# discretefpga.net
KiCad netlist of a schematic drawn in EAGLE
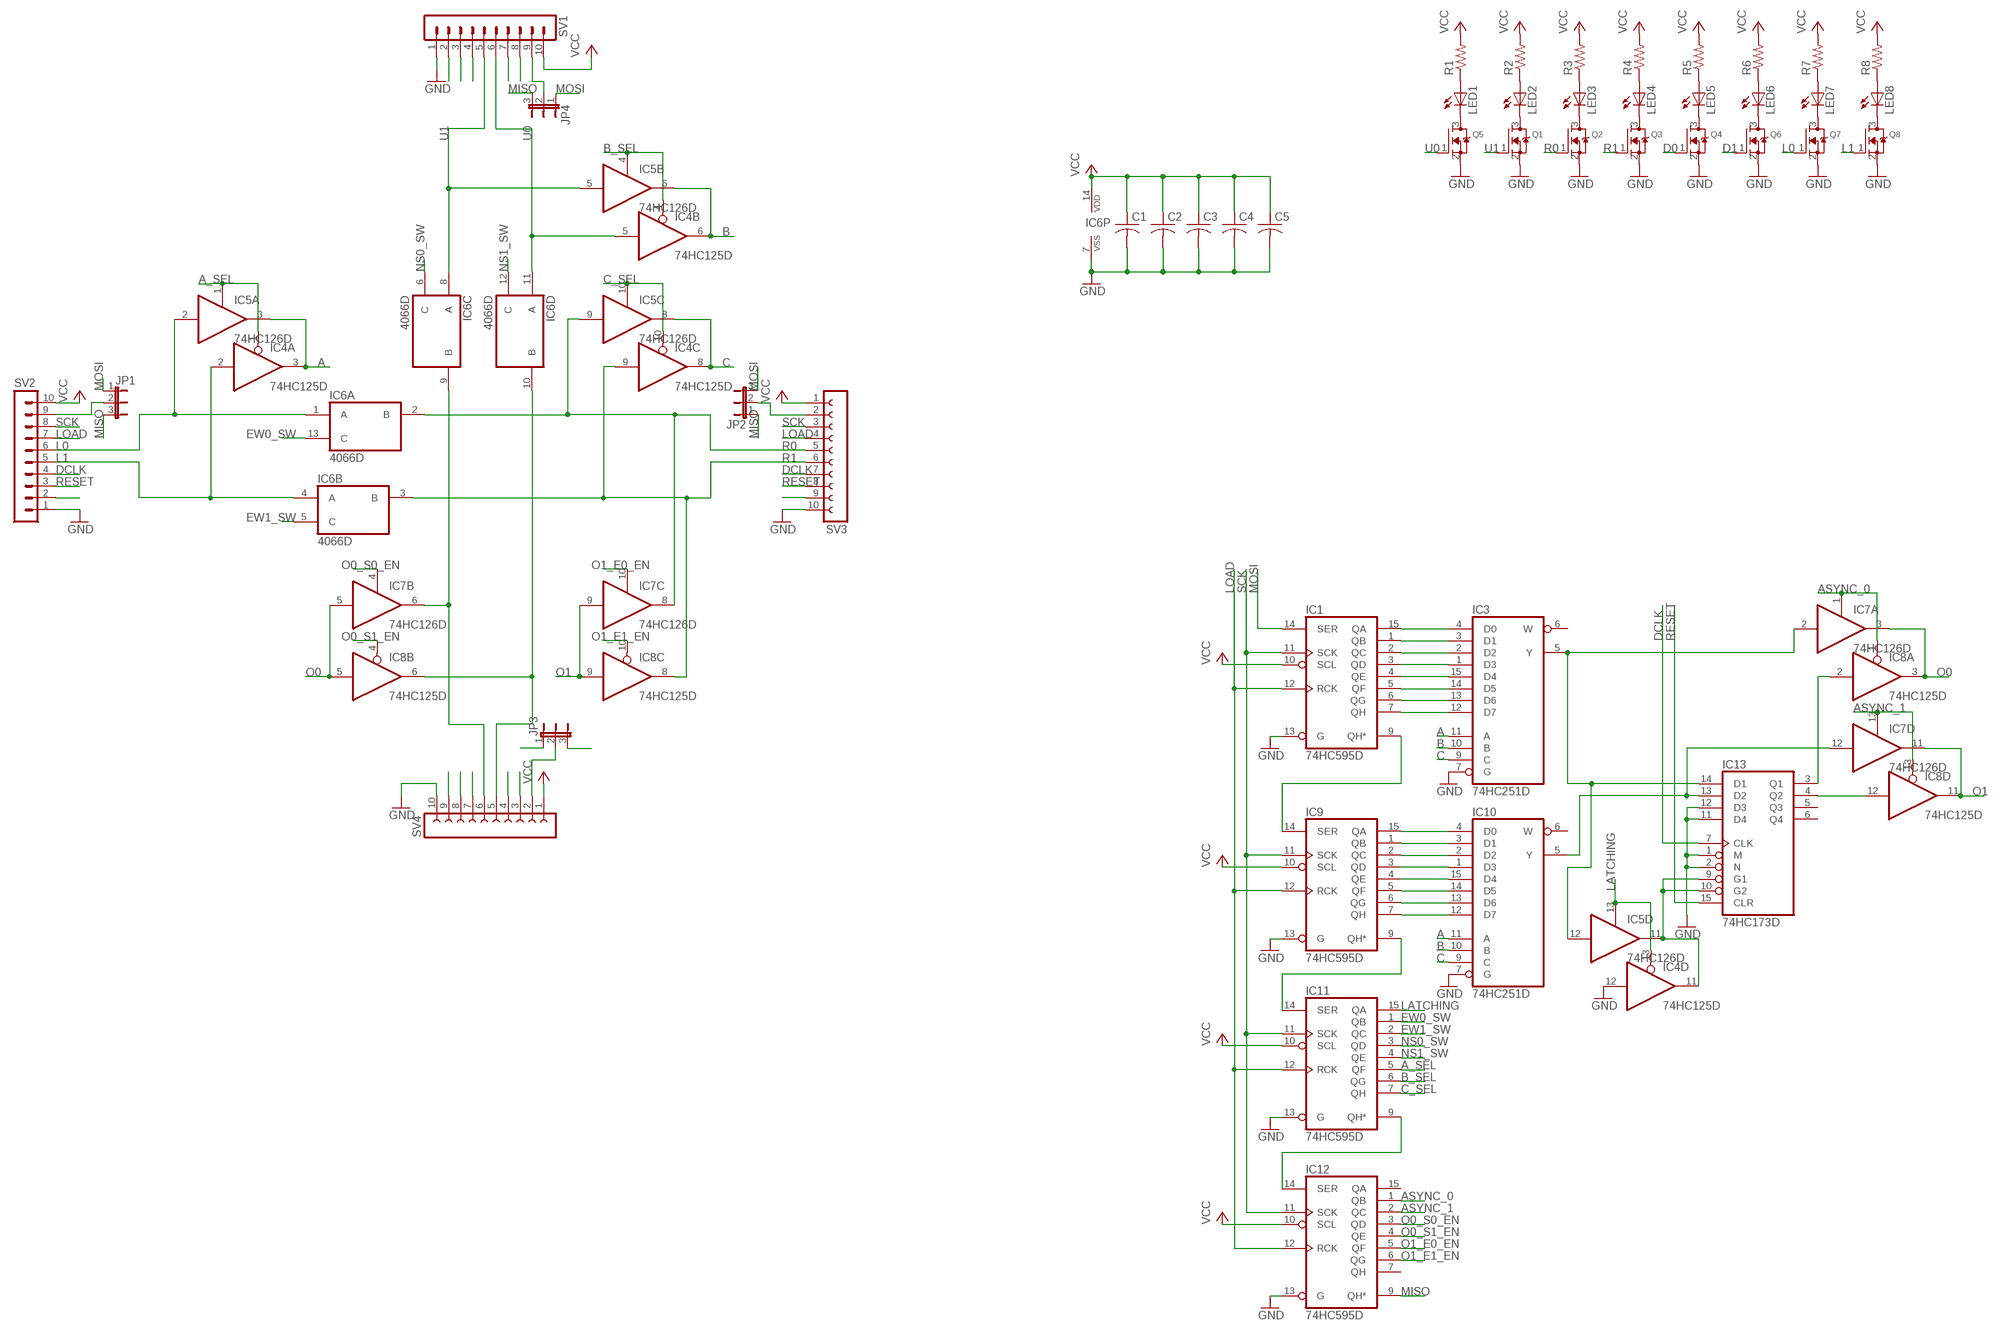
[diagram p0: schematic, sheet 1]

(export (version "E")
  (design (tool "Eeschema 10.0.6"))
  (components
    (comp (ref "C1")
      (value "C-USC0805")
      (footprint "eagle-import:C0805")
      (libsource (lib "eagle-import") (part "C-USC0805"))
    )
    (comp (ref "C2")
      (value "C-USC0805")
      (footprint "eagle-import:C0805")
      (libsource (lib "eagle-import") (part "C-USC0805"))
    )
    (comp (ref "C3")
      (value "C-USC0805")
      (footprint "eagle-import:C0805")
      (libsource (lib "eagle-import") (part "C-USC0805"))
    )
    (comp (ref "C4")
      (value "C-USC0805")
      (footprint "eagle-import:C0805")
      (libsource (lib "eagle-import") (part "C-USC0805"))
    )
    (comp (ref "C5")
      (value "C-USC0805")
      (footprint "eagle-import:C0805")
      (libsource (lib "eagle-import") (part "C-USC0805"))
    )
    (comp (ref "IC1")
      (value "74HC595D")
      (footprint "eagle-import:SO16")
      (libsource (lib "eagle-import") (part "74595DHC"))
    )
    (comp (ref "IC3")
      (value "74HC251D")
      (footprint "eagle-import:SO16")
      (libsource (lib "eagle-import") (part "74251DHC"))
    )
    (comp (ref "IC4")
      (value "74HC125D")
      (footprint "eagle-import:SO14")
      (libsource (lib "eagle-import") (part "74125DHC"))
    )
    (comp (ref "IC5")
      (value "74HC126D")
      (footprint "eagle-import:SO14")
      (libsource (lib "eagle-import") (part "74126DHC"))
    )
    (comp (ref "IC6")
      (value "4066D")
      (footprint "eagle-import:SO14")
      (libsource (lib "eagle-import") (part "4066D"))
    )
    (comp (ref "IC7")
      (value "74HC126D")
      (footprint "eagle-import:SO14")
      (libsource (lib "eagle-import") (part "74126DHC"))
    )
    (comp (ref "IC8")
      (value "74HC125D")
      (footprint "eagle-import:SO14")
      (libsource (lib "eagle-import") (part "74125DHC"))
    )
    (comp (ref "IC9")
      (value "74HC595D")
      (footprint "eagle-import:SO16")
      (libsource (lib "eagle-import") (part "74595DHC"))
    )
    (comp (ref "IC10")
      (value "74HC251D")
      (footprint "eagle-import:SO16")
      (libsource (lib "eagle-import") (part "74251DHC"))
    )
    (comp (ref "IC11")
      (value "74HC595D")
      (footprint "eagle-import:SO16")
      (libsource (lib "eagle-import") (part "74595DHC"))
    )
    (comp (ref "IC12")
      (value "74HC595D")
      (footprint "eagle-import:SO16")
      (libsource (lib "eagle-import") (part "74595DHC"))
    )
    (comp (ref "IC13")
      (value "74HC173D")
      (footprint "eagle-import:SO16")
      (libsource (lib "eagle-import") (part "74173DHC"))
    )
    (comp (ref "JP1")
      (value "JP2E")
      (footprint "eagle-import:JP2")
      (libsource (lib "eagle-import") (part "JP2E"))
    )
    (comp (ref "JP2")
      (value "JP2E")
      (footprint "eagle-import:JP2")
      (libsource (lib "eagle-import") (part "JP2E"))
    )
    (comp (ref "JP3")
      (value "JP2E")
      (footprint "eagle-import:JP2")
      (libsource (lib "eagle-import") (part "JP2E"))
    )
    (comp (ref "JP4")
      (value "JP2E")
      (footprint "eagle-import:JP2")
      (libsource (lib "eagle-import") (part "JP2E"))
    )
    (comp (ref "LED1")
      (value "LEDCHIP-LED0805")
      (footprint "eagle-import:CHIP-LED0805")
      (libsource (lib "eagle-import") (part "LEDCHIP-LED0805"))
    )
    (comp (ref "LED2")
      (value "LEDCHIP-LED0805")
      (footprint "eagle-import:CHIP-LED0805")
      (libsource (lib "eagle-import") (part "LEDCHIP-LED0805"))
    )
    (comp (ref "LED3")
      (value "LEDCHIP-LED0805")
      (footprint "eagle-import:CHIP-LED0805")
      (libsource (lib "eagle-import") (part "LEDCHIP-LED0805"))
    )
    (comp (ref "LED4")
      (value "LEDCHIP-LED0805")
      (footprint "eagle-import:CHIP-LED0805")
      (libsource (lib "eagle-import") (part "LEDCHIP-LED0805"))
    )
    (comp (ref "LED5")
      (value "LEDCHIP-LED0805")
      (footprint "eagle-import:CHIP-LED0805")
      (libsource (lib "eagle-import") (part "LEDCHIP-LED0805"))
    )
    (comp (ref "LED6")
      (value "LEDCHIP-LED0805")
      (footprint "eagle-import:CHIP-LED0805")
      (libsource (lib "eagle-import") (part "LEDCHIP-LED0805"))
    )
    (comp (ref "LED7")
      (value "LEDCHIP-LED0805")
      (footprint "eagle-import:CHIP-LED0805")
      (libsource (lib "eagle-import") (part "LEDCHIP-LED0805"))
    )
    (comp (ref "LED8")
      (value "LEDCHIP-LED0805")
      (footprint "eagle-import:CHIP-LED0805")
      (libsource (lib "eagle-import") (part "LEDCHIP-LED0805"))
    )
    (comp (ref "Q1")
      (value "MOSFET-NREFLOW")
      (footprint "eagle-import:SOT23")
      (libsource (lib "eagle-import") (part "MOSFET-NREFLOW"))
    )
    (comp (ref "Q2")
      (value "MOSFET-NREFLOW")
      (footprint "eagle-import:SOT23")
      (libsource (lib "eagle-import") (part "MOSFET-NREFLOW"))
    )
    (comp (ref "Q3")
      (value "MOSFET-NREFLOW")
      (footprint "eagle-import:SOT23")
      (libsource (lib "eagle-import") (part "MOSFET-NREFLOW"))
    )
    (comp (ref "Q4")
      (value "MOSFET-NREFLOW")
      (footprint "eagle-import:SOT23")
      (libsource (lib "eagle-import") (part "MOSFET-NREFLOW"))
    )
    (comp (ref "Q5")
      (value "MOSFET-NREFLOW")
      (footprint "eagle-import:SOT23")
      (libsource (lib "eagle-import") (part "MOSFET-NREFLOW"))
    )
    (comp (ref "Q6")
      (value "MOSFET-NREFLOW")
      (footprint "eagle-import:SOT23")
      (libsource (lib "eagle-import") (part "MOSFET-NREFLOW"))
    )
    (comp (ref "Q7")
      (value "MOSFET-NREFLOW")
      (footprint "eagle-import:SOT23")
      (libsource (lib "eagle-import") (part "MOSFET-NREFLOW"))
    )
    (comp (ref "Q8")
      (value "MOSFET-NREFLOW")
      (footprint "eagle-import:SOT23")
      (libsource (lib "eagle-import") (part "MOSFET-NREFLOW"))
    )
    (comp (ref "R1")
      (value "R-US_R0805")
      (footprint "eagle-import:R0805")
      (libsource (lib "eagle-import") (part "R-US_R0805"))
    )
    (comp (ref "R2")
      (value "R-US_R0805")
      (footprint "eagle-import:R0805")
      (libsource (lib "eagle-import") (part "R-US_R0805"))
    )
    (comp (ref "R3")
      (value "R-US_R0805")
      (footprint "eagle-import:R0805")
      (libsource (lib "eagle-import") (part "R-US_R0805"))
    )
    (comp (ref "R4")
      (value "R-US_R0805")
      (footprint "eagle-import:R0805")
      (libsource (lib "eagle-import") (part "R-US_R0805"))
    )
    (comp (ref "R5")
      (value "R-US_R0805")
      (footprint "eagle-import:R0805")
      (libsource (lib "eagle-import") (part "R-US_R0805"))
    )
    (comp (ref "R6")
      (value "R-US_R0805")
      (footprint "eagle-import:R0805")
      (libsource (lib "eagle-import") (part "R-US_R0805"))
    )
    (comp (ref "R7")
      (value "R-US_R0805")
      (footprint "eagle-import:R0805")
      (libsource (lib "eagle-import") (part "R-US_R0805"))
    )
    (comp (ref "R8")
      (value "R-US_R0805")
      (footprint "eagle-import:R0805")
      (libsource (lib "eagle-import") (part "R-US_R0805"))
    )
    (comp (ref "SV1")
      (value "MA10-1W")
      (footprint "eagle-import:MA10-1W")
      (libsource (lib "eagle-import") (part "MA10-1W"))
    )
    (comp (ref "SV2")
      (value "MA10-1W")
      (footprint "eagle-import:MA10-1W")
      (libsource (lib "eagle-import") (part "MA10-1W"))
    )
    (comp (ref "SV3")
      (value "FE10W")
      (footprint "eagle-import:FE10W")
      (libsource (lib "eagle-import") (part "FE10W"))
    )
    (comp (ref "SV4")
      (value "FE10W")
      (footprint "eagle-import:FE10W")
      (libsource (lib "eagle-import") (part "FE10W"))
    )
  )
  (nets
    (net (code "1") (name "/A") (class "Default")
      (node (ref "IC10") (pin "11") (pinfunction "A_11") (pintype "input"))
      (node (ref "IC3") (pin "11") (pinfunction "A_11") (pintype "input"))
      (node (ref "IC4") (pin "3") (pinfunction "O_3") (pintype "tri_state"))
      (node (ref "IC5") (pin "3") (pinfunction "O_3") (pintype "output"))
    )
    (net (code "2") (name "/ASYNC_0") (class "Default")
      (node (ref "IC12") (pin "1") (pinfunction "QB_1") (pintype "tri_state"))
      (node (ref "IC7") (pin "1") (pinfunction "OE_1") (pintype "input"))
      (node (ref "IC8") (pin "1") (pinfunction "OE_1") (pintype "input"))
    )
    (net (code "3") (name "/ASYNC_1") (class "Default")
      (node (ref "IC12") (pin "2") (pinfunction "QC_2") (pintype "tri_state"))
      (node (ref "IC7") (pin "13") (pinfunction "OE_13") (pintype "input"))
      (node (ref "IC8") (pin "13") (pinfunction "OE_13") (pintype "input"))
    )
    (net (code "4") (name "/A_SEL") (class "Default")
      (node (ref "IC11") (pin "5") (pinfunction "QF_5") (pintype "tri_state"))
      (node (ref "IC4") (pin "1") (pinfunction "OE_1") (pintype "input"))
      (node (ref "IC5") (pin "1") (pinfunction "OE_1") (pintype "input"))
    )
    (net (code "5") (name "/B") (class "Default")
      (node (ref "IC10") (pin "10") (pinfunction "B_10") (pintype "input"))
      (node (ref "IC3") (pin "10") (pinfunction "B_10") (pintype "input"))
      (node (ref "IC4") (pin "6") (pinfunction "O_6") (pintype "tri_state"))
      (node (ref "IC5") (pin "6") (pinfunction "O_6") (pintype "output"))
    )
    (net (code "6") (name "/B_SEL") (class "Default")
      (node (ref "IC11") (pin "6") (pinfunction "QG_6") (pintype "tri_state"))
      (node (ref "IC4") (pin "4") (pinfunction "OE_4") (pintype "input"))
      (node (ref "IC5") (pin "4") (pinfunction "OE_4") (pintype "input"))
    )
    (net (code "7") (name "/C") (class "Default")
      (node (ref "IC10") (pin "9") (pinfunction "C_9") (pintype "input"))
      (node (ref "IC3") (pin "9") (pinfunction "C_9") (pintype "input"))
      (node (ref "IC4") (pin "8") (pinfunction "O_8") (pintype "tri_state"))
      (node (ref "IC5") (pin "8") (pinfunction "O_8") (pintype "output"))
    )
    (net (code "8") (name "/C_SEL") (class "Default")
      (node (ref "IC11") (pin "7") (pinfunction "QH_7") (pintype "tri_state"))
      (node (ref "IC4") (pin "10") (pinfunction "OE_10") (pintype "input"))
      (node (ref "IC5") (pin "10") (pinfunction "OE_10") (pintype "input"))
    )
    (net (code "9") (name "/D0") (class "Default")
      (node (ref "IC6") (pin "10") (pinfunction "B_10") (pintype "tri_state"))
      (node (ref "IC8") (pin "6") (pinfunction "O_6") (pintype "tri_state"))
      (node (ref "Q4") (pin "1") (pinfunction "G_1") (pintype "bidirectional"))
      (node (ref "SV4") (pin "5") (pinfunction "5_5") (pintype "passive"))
    )
    (net (code "10") (name "/D1") (class "Default")
      (node (ref "IC6") (pin "9") (pinfunction "B_9") (pintype "tri_state"))
      (node (ref "IC7") (pin "6") (pinfunction "O_6") (pintype "output"))
      (node (ref "Q6") (pin "1") (pinfunction "G_1") (pintype "bidirectional"))
      (node (ref "SV4") (pin "6") (pinfunction "6_6") (pintype "passive"))
    )
    (net (code "11") (name "/DCLK") (class "Default")
      (node (ref "IC13") (pin "7") (pinfunction "CLK_7") (pintype "input"))
      (node (ref "SV1") (pin "4") (pinfunction "4_4") (pintype "passive"))
      (node (ref "SV2") (pin "4") (pinfunction "4_4") (pintype "passive"))
      (node (ref "SV3") (pin "7") (pinfunction "7_7") (pintype "passive"))
      (node (ref "SV4") (pin "7") (pinfunction "7_7") (pintype "passive"))
    )
    (net (code "12") (name "/EW0_SW") (class "Default")
      (node (ref "IC11") (pin "1") (pinfunction "QB_1") (pintype "tri_state"))
      (node (ref "IC6") (pin "13") (pinfunction "C_13") (pintype "input"))
    )
    (net (code "13") (name "/EW1_SW") (class "Default")
      (node (ref "IC11") (pin "2") (pinfunction "QC_2") (pintype "tri_state"))
      (node (ref "IC6") (pin "5") (pinfunction "C_5") (pintype "input"))
    )
    (net (code "14") (name "/L0") (class "Default")
      (node (ref "IC5") (pin "2") (pinfunction "I_2") (pintype "input"))
      (node (ref "IC6") (pin "1") (pinfunction "A_1") (pintype "tri_state"))
      (node (ref "Q7") (pin "1") (pinfunction "G_1") (pintype "bidirectional"))
      (node (ref "SV2") (pin "6") (pinfunction "6_6") (pintype "passive"))
    )
    (net (code "15") (name "/L1") (class "Default")
      (node (ref "IC4") (pin "2") (pinfunction "I_2") (pintype "input"))
      (node (ref "IC6") (pin "4") (pinfunction "A_4") (pintype "tri_state"))
      (node (ref "Q8") (pin "1") (pinfunction "G_1") (pintype "bidirectional"))
      (node (ref "SV2") (pin "5") (pinfunction "5_5") (pintype "passive"))
    )
    (net (code "16") (name "/LATCHING") (class "Default")
      (node (ref "IC11") (pin "15") (pinfunction "QA_15") (pintype "tri_state"))
      (node (ref "IC4") (pin "13") (pinfunction "OE_13") (pintype "input"))
      (node (ref "IC5") (pin "13") (pinfunction "OE_13") (pintype "input"))
    )
    (net (code "17") (name "/LOAD") (class "Default")
      (node (ref "IC1") (pin "12") (pinfunction "RCK_12") (pintype "input"))
      (node (ref "IC11") (pin "12") (pinfunction "RCK_12") (pintype "input"))
      (node (ref "IC12") (pin "12") (pinfunction "RCK_12") (pintype "input"))
      (node (ref "IC9") (pin "12") (pinfunction "RCK_12") (pintype "input"))
      (node (ref "SV1") (pin "7") (pinfunction "7_7") (pintype "passive"))
      (node (ref "SV2") (pin "7") (pinfunction "7_7") (pintype "passive"))
      (node (ref "SV3") (pin "4") (pinfunction "4_4") (pintype "passive"))
      (node (ref "SV4") (pin "4") (pinfunction "4_4") (pintype "passive"))
    )
    (net (code "18") (name "/MISO") (class "Default")
      (node (ref "IC12") (pin "9") (pinfunction "QH*_9") (pintype "tri_state"))
      (node (ref "JP1") (pin "3") (pinfunction "3_3") (pintype "passive"))
      (node (ref "JP2") (pin "1") (pinfunction "1_1") (pintype "passive"))
      (node (ref "JP3") (pin "1") (pinfunction "1_1") (pintype "passive"))
      (node (ref "JP4") (pin "3") (pinfunction "3_3") (pintype "passive"))
    )
    (net (code "19") (name "/MOSI") (class "Default")
      (node (ref "IC1") (pin "14") (pinfunction "SER_14") (pintype "input"))
      (node (ref "JP1") (pin "1") (pinfunction "1_1") (pintype "passive"))
      (node (ref "JP2") (pin "3") (pinfunction "3_3") (pintype "passive"))
      (node (ref "JP3") (pin "3") (pinfunction "3_3") (pintype "passive"))
      (node (ref "JP4") (pin "1") (pinfunction "1_1") (pintype "passive"))
    )
    (net (code "20") (name "/NS0_SW") (class "Default")
      (node (ref "IC11") (pin "3") (pinfunction "QD_3") (pintype "tri_state"))
      (node (ref "IC6") (pin "6") (pinfunction "C_6") (pintype "input"))
    )
    (net (code "21") (name "/NS1_SW") (class "Default")
      (node (ref "IC11") (pin "4") (pinfunction "QE_4") (pintype "tri_state"))
      (node (ref "IC6") (pin "12") (pinfunction "C_12") (pintype "input"))
    )
    (net (code "22") (name "/O0") (class "Default")
      (node (ref "IC7") (pin "3") (pinfunction "O_3") (pintype "output"))
      (node (ref "IC7") (pin "5") (pinfunction "I_5") (pintype "input"))
      (node (ref "IC8") (pin "3") (pinfunction "O_3") (pintype "tri_state"))
      (node (ref "IC8") (pin "5") (pinfunction "I_5") (pintype "input"))
    )
    (net (code "23") (name "/O0_S0_EN") (class "Default")
      (node (ref "IC12") (pin "3") (pinfunction "QD_3") (pintype "tri_state"))
      (node (ref "IC7") (pin "4") (pinfunction "OE_4") (pintype "input"))
    )
    (net (code "24") (name "/O0_S1_EN") (class "Default")
      (node (ref "IC12") (pin "4") (pinfunction "QE_4") (pintype "tri_state"))
      (node (ref "IC8") (pin "4") (pinfunction "OE_4") (pintype "input"))
    )
    (net (code "25") (name "/O1") (class "Default")
      (node (ref "IC7") (pin "11") (pinfunction "O_11") (pintype "output"))
      (node (ref "IC7") (pin "9") (pinfunction "I_9") (pintype "input"))
      (node (ref "IC8") (pin "11") (pinfunction "O_11") (pintype "tri_state"))
      (node (ref "IC8") (pin "9") (pinfunction "I_9") (pintype "input"))
    )
    (net (code "26") (name "/O1_E0_EN") (class "Default")
      (node (ref "IC12") (pin "5") (pinfunction "QF_5") (pintype "tri_state"))
      (node (ref "IC7") (pin "10") (pinfunction "OE_10") (pintype "input"))
    )
    (net (code "27") (name "/O1_E1_EN") (class "Default")
      (node (ref "IC12") (pin "6") (pinfunction "QG_6") (pintype "tri_state"))
      (node (ref "IC8") (pin "10") (pinfunction "OE_10") (pintype "input"))
    )
    (net (code "28") (name "/R0") (class "Default")
      (node (ref "IC5") (pin "9") (pinfunction "I_9") (pintype "input"))
      (node (ref "IC6") (pin "2") (pinfunction "B_2") (pintype "tri_state"))
      (node (ref "IC7") (pin "8") (pinfunction "O_8") (pintype "output"))
      (node (ref "Q2") (pin "1") (pinfunction "G_1") (pintype "bidirectional"))
      (node (ref "SV3") (pin "5") (pinfunction "5_5") (pintype "passive"))
    )
    (net (code "29") (name "/R1") (class "Default")
      (node (ref "IC4") (pin "9") (pinfunction "I_9") (pintype "input"))
      (node (ref "IC6") (pin "3") (pinfunction "B_3") (pintype "tri_state"))
      (node (ref "IC8") (pin "8") (pinfunction "O_8") (pintype "tri_state"))
      (node (ref "Q3") (pin "1") (pinfunction "G_1") (pintype "bidirectional"))
      (node (ref "SV3") (pin "6") (pinfunction "6_6") (pintype "passive"))
    )
    (net (code "30") (name "/RESET") (class "Default")
      (node (ref "IC13") (pin "15") (pinfunction "CLR_15") (pintype "input"))
      (node (ref "SV1") (pin "3") (pinfunction "3_3") (pintype "passive"))
      (node (ref "SV2") (pin "3") (pinfunction "3_3") (pintype "passive"))
      (node (ref "SV3") (pin "8") (pinfunction "8_8") (pintype "passive"))
      (node (ref "SV4") (pin "8") (pinfunction "8_8") (pintype "passive"))
    )
    (net (code "31") (name "/SCK") (class "Default")
      (node (ref "IC1") (pin "11") (pinfunction "SCK_11") (pintype "input"))
      (node (ref "IC11") (pin "11") (pinfunction "SCK_11") (pintype "input"))
      (node (ref "IC12") (pin "11") (pinfunction "SCK_11") (pintype "input"))
      (node (ref "IC9") (pin "11") (pinfunction "SCK_11") (pintype "input"))
      (node (ref "SV1") (pin "8") (pinfunction "8_8") (pintype "passive"))
      (node (ref "SV2") (pin "8") (pinfunction "8_8") (pintype "passive"))
      (node (ref "SV3") (pin "3") (pinfunction "3_3") (pintype "passive"))
      (node (ref "SV4") (pin "3") (pinfunction "3_3") (pintype "passive"))
    )
    (net (code "32") (name "/U0") (class "Default")
      (node (ref "IC4") (pin "5") (pinfunction "I_5") (pintype "input"))
      (node (ref "IC6") (pin "11") (pinfunction "A_11") (pintype "tri_state"))
      (node (ref "Q5") (pin "1") (pinfunction "G_1") (pintype "bidirectional"))
      (node (ref "SV1") (pin "6") (pinfunction "6_6") (pintype "passive"))
    )
    (net (code "33") (name "/U1") (class "Default")
      (node (ref "IC5") (pin "5") (pinfunction "I_5") (pintype "input"))
      (node (ref "IC6") (pin "8") (pinfunction "A_8") (pintype "tri_state"))
      (node (ref "Q1") (pin "1") (pinfunction "G_1") (pintype "bidirectional"))
      (node (ref "SV1") (pin "5") (pinfunction "5_5") (pintype "passive"))
    )
    (net (code "34") (name "GND") (class "Default")
      (node (ref "C1") (pin "2") (pinfunction "2_2") (pintype "passive"))
      (node (ref "C2") (pin "2") (pinfunction "2_2") (pintype "passive"))
      (node (ref "C3") (pin "2") (pinfunction "2_2") (pintype "passive"))
      (node (ref "C4") (pin "2") (pinfunction "2_2") (pintype "passive"))
      (node (ref "C5") (pin "2") (pinfunction "2_2") (pintype "passive"))
      (node (ref "IC1") (pin "13") (pinfunction "G_13") (pintype "input"))
      (node (ref "IC10") (pin "7") (pinfunction "G_7") (pintype "input"))
      (node (ref "IC11") (pin "13") (pinfunction "G_13") (pintype "input"))
      (node (ref "IC12") (pin "13") (pinfunction "G_13") (pintype "input"))
      (node (ref "IC13") (pin "1") (pinfunction "M_1") (pintype "input"))
      (node (ref "IC13") (pin "11") (pinfunction "D4_11") (pintype "input"))
      (node (ref "IC13") (pin "12") (pinfunction "D3_12") (pintype "input"))
      (node (ref "IC13") (pin "2") (pinfunction "N_2") (pintype "input"))
      (node (ref "IC3") (pin "7") (pinfunction "G_7") (pintype "input"))
      (node (ref "IC4") (pin "12") (pinfunction "I_12") (pintype "input"))
      (node (ref "IC6") (pin "7") (pinfunction "VSS_7") (pintype "power_in"))
      (node (ref "IC9") (pin "13") (pinfunction "G_13") (pintype "input"))
      (node (ref "Q1") (pin "2") (pinfunction "S_2") (pintype "bidirectional"))
      (node (ref "Q2") (pin "2") (pinfunction "S_2") (pintype "bidirectional"))
      (node (ref "Q3") (pin "2") (pinfunction "S_2") (pintype "bidirectional"))
      (node (ref "Q4") (pin "2") (pinfunction "S_2") (pintype "bidirectional"))
      (node (ref "Q5") (pin "2") (pinfunction "S_2") (pintype "bidirectional"))
      (node (ref "Q6") (pin "2") (pinfunction "S_2") (pintype "bidirectional"))
      (node (ref "Q7") (pin "2") (pinfunction "S_2") (pintype "bidirectional"))
      (node (ref "Q8") (pin "2") (pinfunction "S_2") (pintype "bidirectional"))
      (node (ref "SV1") (pin "1") (pinfunction "1_1") (pintype "passive"))
      (node (ref "SV2") (pin "1") (pinfunction "1_1") (pintype "passive"))
      (node (ref "SV3") (pin "10") (pinfunction "10_10") (pintype "passive"))
      (node (ref "SV4") (pin "10") (pinfunction "10_10") (pintype "passive"))
    )
    (net (code "35") (name "Net-(IC1A-QA)") (class "Default")
      (node (ref "IC1") (pin "15") (pinfunction "QA_15") (pintype "tri_state"))
      (node (ref "IC3") (pin "4") (pinfunction "D0_4") (pintype "input"))
    )
    (net (code "36") (name "Net-(IC1A-QB)") (class "Default")
      (node (ref "IC1") (pin "1") (pinfunction "QB_1") (pintype "tri_state"))
      (node (ref "IC3") (pin "3") (pinfunction "D1_3") (pintype "input"))
    )
    (net (code "37") (name "Net-(IC1A-QC)") (class "Default")
      (node (ref "IC1") (pin "2") (pinfunction "QC_2") (pintype "tri_state"))
      (node (ref "IC3") (pin "2") (pinfunction "D2_2") (pintype "input"))
    )
    (net (code "38") (name "Net-(IC1A-QD)") (class "Default")
      (node (ref "IC1") (pin "3") (pinfunction "QD_3") (pintype "tri_state"))
      (node (ref "IC3") (pin "1") (pinfunction "D3_1") (pintype "input"))
    )
    (net (code "39") (name "Net-(IC1A-QE)") (class "Default")
      (node (ref "IC1") (pin "4") (pinfunction "QE_4") (pintype "tri_state"))
      (node (ref "IC3") (pin "15") (pinfunction "D4_15") (pintype "input"))
    )
    (net (code "40") (name "Net-(IC1A-QF)") (class "Default")
      (node (ref "IC1") (pin "5") (pinfunction "QF_5") (pintype "tri_state"))
      (node (ref "IC3") (pin "14") (pinfunction "D5_14") (pintype "input"))
    )
    (net (code "41") (name "Net-(IC1A-QG)") (class "Default")
      (node (ref "IC1") (pin "6") (pinfunction "QG_6") (pintype "tri_state"))
      (node (ref "IC3") (pin "13") (pinfunction "D6_13") (pintype "input"))
    )
    (net (code "42") (name "Net-(IC1A-QH)") (class "Default")
      (node (ref "IC1") (pin "7") (pinfunction "QH_7") (pintype "tri_state"))
      (node (ref "IC3") (pin "12") (pinfunction "D7_12") (pintype "input"))
    )
    (net (code "43") (name "Net-(IC1A-QH*)") (class "Default")
      (node (ref "IC1") (pin "9") (pinfunction "QH*_9") (pintype "tri_state"))
      (node (ref "IC9") (pin "14") (pinfunction "SER_14") (pintype "input"))
    )
    (net (code "44") (name "Net-(IC10A-D0)") (class "Default")
      (node (ref "IC10") (pin "4") (pinfunction "D0_4") (pintype "input"))
      (node (ref "IC9") (pin "15") (pinfunction "QA_15") (pintype "tri_state"))
    )
    (net (code "45") (name "Net-(IC10A-D1)") (class "Default")
      (node (ref "IC10") (pin "3") (pinfunction "D1_3") (pintype "input"))
      (node (ref "IC9") (pin "1") (pinfunction "QB_1") (pintype "tri_state"))
    )
    (net (code "46") (name "Net-(IC10A-D2)") (class "Default")
      (node (ref "IC10") (pin "2") (pinfunction "D2_2") (pintype "input"))
      (node (ref "IC9") (pin "2") (pinfunction "QC_2") (pintype "tri_state"))
    )
    (net (code "47") (name "Net-(IC10A-D3)") (class "Default")
      (node (ref "IC10") (pin "1") (pinfunction "D3_1") (pintype "input"))
      (node (ref "IC9") (pin "3") (pinfunction "QD_3") (pintype "tri_state"))
    )
    (net (code "48") (name "Net-(IC10A-D4)") (class "Default")
      (node (ref "IC10") (pin "15") (pinfunction "D4_15") (pintype "input"))
      (node (ref "IC9") (pin "4") (pinfunction "QE_4") (pintype "tri_state"))
    )
    (net (code "49") (name "Net-(IC10A-D5)") (class "Default")
      (node (ref "IC10") (pin "14") (pinfunction "D5_14") (pintype "input"))
      (node (ref "IC9") (pin "5") (pinfunction "QF_5") (pintype "tri_state"))
    )
    (net (code "50") (name "Net-(IC10A-D6)") (class "Default")
      (node (ref "IC10") (pin "13") (pinfunction "D6_13") (pintype "input"))
      (node (ref "IC9") (pin "6") (pinfunction "QG_6") (pintype "tri_state"))
    )
    (net (code "51") (name "Net-(IC10A-D7)") (class "Default")
      (node (ref "IC10") (pin "12") (pinfunction "D7_12") (pintype "input"))
      (node (ref "IC9") (pin "7") (pinfunction "QH_7") (pintype "tri_state"))
    )
    (net (code "52") (name "Net-(IC10A-Y)") (class "Default")
      (node (ref "IC10") (pin "5") (pinfunction "Y_5") (pintype "tri_state"))
      (node (ref "IC13") (pin "13") (pinfunction "D2_13") (pintype "input"))
      (node (ref "IC7") (pin "12") (pinfunction "I_12") (pintype "input"))
    )
    (net (code "53") (name "Net-(IC11A-QH*)") (class "Default")
      (node (ref "IC11") (pin "9") (pinfunction "QH*_9") (pintype "tri_state"))
      (node (ref "IC12") (pin "14") (pinfunction "SER_14") (pintype "input"))
    )
    (net (code "54") (name "Net-(IC11A-SER)") (class "Default")
      (node (ref "IC11") (pin "14") (pinfunction "SER_14") (pintype "input"))
      (node (ref "IC9") (pin "9") (pinfunction "QH*_9") (pintype "tri_state"))
    )
    (net (code "55") (name "Net-(IC13A-D1)") (class "Default")
      (node (ref "IC13") (pin "14") (pinfunction "D1_14") (pintype "input"))
      (node (ref "IC3") (pin "5") (pinfunction "Y_5") (pintype "tri_state"))
      (node (ref "IC5") (pin "12") (pinfunction "I_12") (pintype "input"))
      (node (ref "IC7") (pin "2") (pinfunction "I_2") (pintype "input"))
    )
    (net (code "56") (name "Net-(IC13A-G1)") (class "Default")
      (node (ref "IC13") (pin "10") (pinfunction "G2_10") (pintype "input"))
      (node (ref "IC13") (pin "9") (pinfunction "G1_9") (pintype "input"))
      (node (ref "IC4") (pin "11") (pinfunction "O_11") (pintype "tri_state"))
      (node (ref "IC5") (pin "11") (pinfunction "O_11") (pintype "output"))
    )
    (net (code "57") (name "Net-(IC13A-Q1)") (class "Default")
      (node (ref "IC13") (pin "3") (pinfunction "Q1_3") (pintype "tri_state"))
      (node (ref "IC8") (pin "2") (pinfunction "I_2") (pintype "input"))
    )
    (net (code "58") (name "Net-(IC13A-Q2)") (class "Default")
      (node (ref "IC13") (pin "4") (pinfunction "Q2_4") (pintype "tri_state"))
      (node (ref "IC8") (pin "12") (pinfunction "I_12") (pintype "input"))
    )
    (net (code "59") (name "Net-(JP1-Pad2)") (class "Default")
      (node (ref "JP1") (pin "2") (pinfunction "2_2") (pintype "passive"))
      (node (ref "SV2") (pin "9") (pinfunction "9_9") (pintype "passive"))
    )
    (net (code "60") (name "Net-(JP2-Pad2)") (class "Default")
      (node (ref "JP2") (pin "2") (pinfunction "2_2") (pintype "passive"))
      (node (ref "SV3") (pin "2") (pinfunction "2_2") (pintype "passive"))
    )
    (net (code "61") (name "Net-(JP3-Pad2)") (class "Default")
      (node (ref "JP3") (pin "2") (pinfunction "2_2") (pintype "passive"))
      (node (ref "SV4") (pin "2") (pinfunction "2_2") (pintype "passive"))
    )
    (net (code "62") (name "Net-(JP4-Pad2)") (class "Default")
      (node (ref "JP4") (pin "2") (pinfunction "2_2") (pintype "passive"))
      (node (ref "SV1") (pin "9") (pinfunction "9_9") (pintype "passive"))
    )
    (net (code "63") (name "Net-(LED1-PadA)") (class "Default")
      (node (ref "LED1") (pin "A") (pinfunction "A_A") (pintype "passive"))
      (node (ref "R1") (pin "1") (pinfunction "1_1") (pintype "passive"))
    )
    (net (code "64") (name "Net-(LED2-PadA)") (class "Default")
      (node (ref "LED2") (pin "A") (pinfunction "A_A") (pintype "passive"))
      (node (ref "R2") (pin "1") (pinfunction "1_1") (pintype "passive"))
    )
    (net (code "65") (name "Net-(LED3-PadA)") (class "Default")
      (node (ref "LED3") (pin "A") (pinfunction "A_A") (pintype "passive"))
      (node (ref "R3") (pin "1") (pinfunction "1_1") (pintype "passive"))
    )
    (net (code "66") (name "Net-(LED4-PadA)") (class "Default")
      (node (ref "LED4") (pin "A") (pinfunction "A_A") (pintype "passive"))
      (node (ref "R4") (pin "1") (pinfunction "1_1") (pintype "passive"))
    )
    (net (code "67") (name "Net-(LED5-PadA)") (class "Default")
      (node (ref "LED5") (pin "A") (pinfunction "A_A") (pintype "passive"))
      (node (ref "R5") (pin "1") (pinfunction "1_1") (pintype "passive"))
    )
    (net (code "68") (name "Net-(LED6-PadA)") (class "Default")
      (node (ref "LED6") (pin "A") (pinfunction "A_A") (pintype "passive"))
      (node (ref "R6") (pin "1") (pinfunction "1_1") (pintype "passive"))
    )
    (net (code "69") (name "Net-(LED7-PadA)") (class "Default")
      (node (ref "LED7") (pin "A") (pinfunction "A_A") (pintype "passive"))
      (node (ref "R7") (pin "1") (pinfunction "1_1") (pintype "passive"))
    )
    (net (code "70") (name "Net-(LED8-PadA)") (class "Default")
      (node (ref "LED8") (pin "A") (pinfunction "A_A") (pintype "passive"))
      (node (ref "R8") (pin "1") (pinfunction "1_1") (pintype "passive"))
    )
    (net (code "71") (name "Net-(Q1-D)") (class "Default")
      (node (ref "LED2") (pin "C") (pinfunction "C_C") (pintype "passive"))
      (node (ref "Q1") (pin "3") (pinfunction "D_3") (pintype "bidirectional"))
    )
    (net (code "72") (name "Net-(Q2-D)") (class "Default")
      (node (ref "LED3") (pin "C") (pinfunction "C_C") (pintype "passive"))
      (node (ref "Q2") (pin "3") (pinfunction "D_3") (pintype "bidirectional"))
    )
    (net (code "73") (name "Net-(Q3-D)") (class "Default")
      (node (ref "LED4") (pin "C") (pinfunction "C_C") (pintype "passive"))
      (node (ref "Q3") (pin "3") (pinfunction "D_3") (pintype "bidirectional"))
    )
    (net (code "74") (name "Net-(Q4-D)") (class "Default")
      (node (ref "LED5") (pin "C") (pinfunction "C_C") (pintype "passive"))
      (node (ref "Q4") (pin "3") (pinfunction "D_3") (pintype "bidirectional"))
    )
    (net (code "75") (name "Net-(Q5-D)") (class "Default")
      (node (ref "LED1") (pin "C") (pinfunction "C_C") (pintype "passive"))
      (node (ref "Q5") (pin "3") (pinfunction "D_3") (pintype "bidirectional"))
    )
    (net (code "76") (name "Net-(Q6-D)") (class "Default")
      (node (ref "LED6") (pin "C") (pinfunction "C_C") (pintype "passive"))
      (node (ref "Q6") (pin "3") (pinfunction "D_3") (pintype "bidirectional"))
    )
    (net (code "77") (name "Net-(Q7-D)") (class "Default")
      (node (ref "LED7") (pin "C") (pinfunction "C_C") (pintype "passive"))
      (node (ref "Q7") (pin "3") (pinfunction "D_3") (pintype "bidirectional"))
    )
    (net (code "78") (name "Net-(Q8-D)") (class "Default")
      (node (ref "LED8") (pin "C") (pinfunction "C_C") (pintype "passive"))
      (node (ref "Q8") (pin "3") (pinfunction "D_3") (pintype "bidirectional"))
    )
    (net (code "79") (name "VCC") (class "Default")
      (node (ref "C1") (pin "1") (pinfunction "1_1") (pintype "passive"))
      (node (ref "C2") (pin "1") (pinfunction "1_1") (pintype "passive"))
      (node (ref "C3") (pin "1") (pinfunction "1_1") (pintype "passive"))
      (node (ref "C4") (pin "1") (pinfunction "1_1") (pintype "passive"))
      (node (ref "C5") (pin "1") (pinfunction "1_1") (pintype "passive"))
      (node (ref "IC1") (pin "10") (pinfunction "SCL_10") (pintype "input"))
      (node (ref "IC11") (pin "10") (pinfunction "SCL_10") (pintype "input"))
      (node (ref "IC12") (pin "10") (pinfunction "SCL_10") (pintype "input"))
      (node (ref "IC6") (pin "14") (pinfunction "VDD_14") (pintype "power_in"))
      (node (ref "IC9") (pin "10") (pinfunction "SCL_10") (pintype "input"))
      (node (ref "R1") (pin "2") (pinfunction "2_2") (pintype "passive"))
      (node (ref "R2") (pin "2") (pinfunction "2_2") (pintype "passive"))
      (node (ref "R3") (pin "2") (pinfunction "2_2") (pintype "passive"))
      (node (ref "R4") (pin "2") (pinfunction "2_2") (pintype "passive"))
      (node (ref "R5") (pin "2") (pinfunction "2_2") (pintype "passive"))
      (node (ref "R6") (pin "2") (pinfunction "2_2") (pintype "passive"))
      (node (ref "R7") (pin "2") (pinfunction "2_2") (pintype "passive"))
      (node (ref "R8") (pin "2") (pinfunction "2_2") (pintype "passive"))
      (node (ref "SV1") (pin "10") (pinfunction "10_10") (pintype "passive"))
      (node (ref "SV2") (pin "10") (pinfunction "10_10") (pintype "passive"))
      (node (ref "SV3") (pin "1") (pinfunction "1_1") (pintype "passive"))
      (node (ref "SV4") (pin "1") (pinfunction "1_1") (pintype "passive"))
    )
    (net (code "80") (name "unconnected-(IC3A-W-Pad6)") (class "Default")
      (node (ref "IC3") (pin "6") (pinfunction "W_6") (pintype "tri_state"))
    )
    (net (code "81") (name "unconnected-(IC10A-W-Pad6)") (class "Default")
      (node (ref "IC10") (pin "6") (pinfunction "W_6") (pintype "tri_state"))
    )
    (net (code "82") (name "unconnected-(IC12A-QA-Pad15)") (class "Default")
      (node (ref "IC12") (pin "15") (pinfunction "QA_15") (pintype "tri_state"))
    )
    (net (code "83") (name "unconnected-(IC12A-QH-Pad7)") (class "Default")
      (node (ref "IC12") (pin "7") (pinfunction "QH_7") (pintype "tri_state"))
    )
    (net (code "84") (name "unconnected-(IC13A-Q3-Pad5)") (class "Default")
      (node (ref "IC13") (pin "5") (pinfunction "Q3_5") (pintype "tri_state"))
    )
    (net (code "85") (name "unconnected-(IC13A-Q4-Pad6)") (class "Default")
      (node (ref "IC13") (pin "6") (pinfunction "Q4_6") (pintype "tri_state"))
    )
    (net (code "86") (name "unconnected-(SV1-Pad2)") (class "Default")
      (node (ref "SV1") (pin "2") (pinfunction "2_2") (pintype "passive"))
    )
    (net (code "87") (name "unconnected-(SV2-Pad2)") (class "Default")
      (node (ref "SV2") (pin "2") (pinfunction "2_2") (pintype "passive"))
    )
    (net (code "88") (name "unconnected-(SV3-Pad9)") (class "Default")
      (node (ref "SV3") (pin "9") (pinfunction "9_9") (pintype "passive"))
    )
    (net (code "89") (name "unconnected-(SV4-Pad9)") (class "Default")
      (node (ref "SV4") (pin "9") (pinfunction "9_9") (pintype "passive"))
    )
  )
)
